# stm32f103.net
KiCad netlist of a schematic drawn in Altium Designer
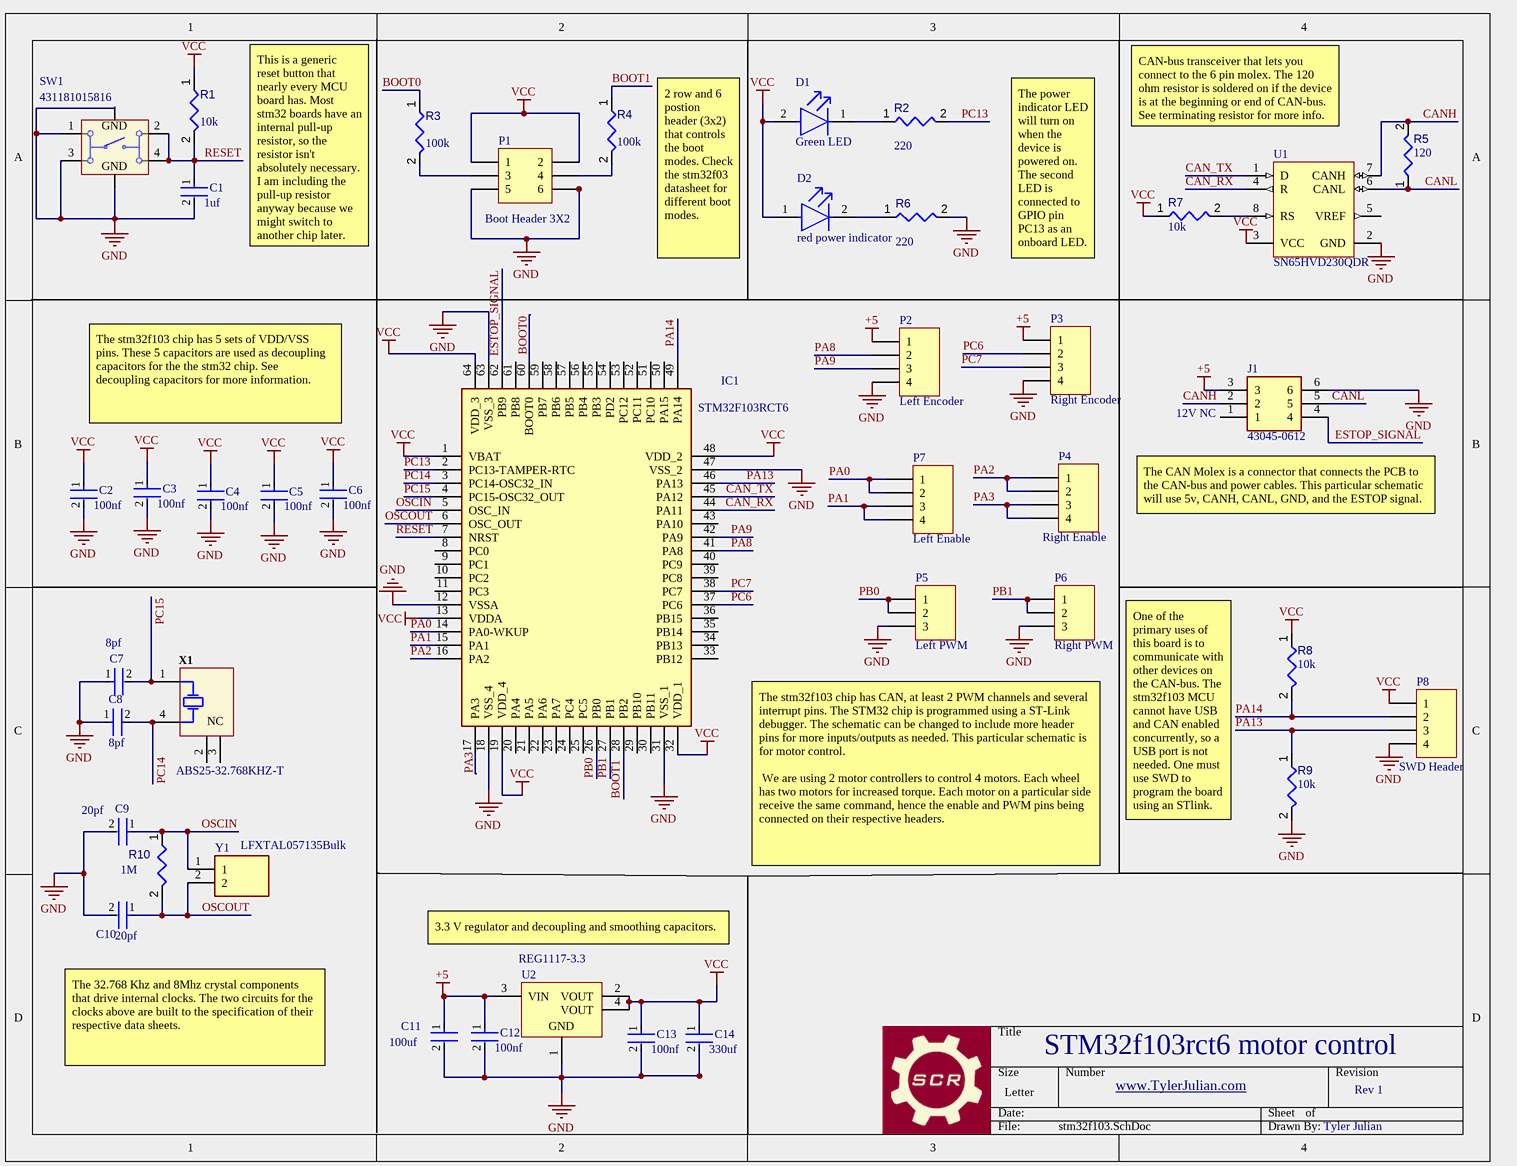
[diagram p0: stm32f103.SchDoc]

(export (version "E")
  (design (tool "Eeschema 10.0.6"))
  (components
    (comp (ref "C1")
      (value "1uf")
      (footprint "FP-GCJ21B-0_3-MFG")
      (description "Multilayer Ceramic Capacitors MLCC - SMD/SMT 0805 1uF 10%, 25VDC,  X7R 15%")
      (fields (field (name "TOLERANCE") "10%"))
      (libsource (lib "Altium Content Vault") (part "02cd4be3c70576c341d710602a673aa"))
    )
    (comp (ref "C2")
      (value "100nf")
      (footprint "FP-GCJ21B-0_3-MFG")
      (description "Multilayer Ceramic Capacitors MLCC - SMD/SMT 0805 1uF 10%, 25VDC,  X7R 15%")
      (fields (field (name "TOLERANCE") "10%"))
      (libsource (lib "Altium Content Vault") (part "02cd4be3c70576c341d710602a673aa"))
    )
    (comp (ref "C3")
      (value "100nf")
      (footprint "FP-GCJ21B-0_3-MFG")
      (description "Multilayer Ceramic Capacitors MLCC - SMD/SMT 0805 1uF 10%, 25VDC,  X7R 15%")
      (fields (field (name "TOLERANCE") "10%"))
      (libsource (lib "Altium Content Vault") (part "02cd4be3c70576c341d710602a673aa"))
    )
    (comp (ref "C4")
      (value "100nf")
      (footprint "FP-GCJ21B-0_3-MFG")
      (description "Multilayer Ceramic Capacitors MLCC - SMD/SMT 0805 1uF 10%, 25VDC,  X7R 15%")
      (fields (field (name "TOLERANCE") "10%"))
      (libsource (lib "Altium Content Vault") (part "02cd4be3c70576c341d710602a673aa"))
    )
    (comp (ref "C5")
      (value "100nf")
      (footprint "FP-GCJ21B-0_3-MFG")
      (description "Multilayer Ceramic Capacitors MLCC - SMD/SMT 0805 1uF 10%, 25VDC,  X7R 15%")
      (fields (field (name "TOLERANCE") "10%"))
      (libsource (lib "Altium Content Vault") (part "02cd4be3c70576c341d710602a673aa"))
    )
    (comp (ref "C6")
      (value "100nf")
      (footprint "FP-GCJ21B-0_3-MFG")
      (description "Multilayer Ceramic Capacitors MLCC - SMD/SMT 0805 1uF 10%, 25VDC,  X7R 15%")
      (fields (field (name "TOLERANCE") "10%"))
      (libsource (lib "Altium Content Vault") (part "02cd4be3c70576c341d710602a673aa"))
    )
    (comp (ref "C7")
      (value "8pf")
      (footprint "FP-GCJ21B-0_3-MFG")
      (description "Multilayer Ceramic Capacitors MLCC - SMD/SMT 0805 1uF 10%, 25VDC,  X7R 15%")
      (fields (field (name "TOLERANCE") "10%"))
      (libsource (lib "Altium Content Vault") (part "02cd4be3c70576c341d710602a673aa"))
    )
    (comp (ref "C8")
      (value "8pf")
      (footprint "FP-GCJ21B-0_3-MFG")
      (description "Multilayer Ceramic Capacitors MLCC - SMD/SMT 0805 1uF 10%, 25VDC,  X7R 15%")
      (fields (field (name "TOLERANCE") "10%"))
      (libsource (lib "Altium Content Vault") (part "02cd4be3c70576c341d710602a673aa"))
    )
    (comp (ref "C9")
      (value "20pf")
      (footprint "FP-GCJ21B-0_3-MFG")
      (description "Multilayer Ceramic Capacitors MLCC - SMD/SMT 0805 1uF 10%, 25VDC,  X7R 15%")
      (fields (field (name "TOLERANCE") "10%"))
      (libsource (lib "Altium Content Vault") (part "02cd4be3c70576c341d710602a673aa"))
    )
    (comp (ref "C10")
      (value "20pf")
      (footprint "FP-GCJ21B-0_3-MFG")
      (description "Multilayer Ceramic Capacitors MLCC - SMD/SMT 0805 1uF 10%, 25VDC,  X7R 15%")
      (fields (field (name "TOLERANCE") "10%"))
      (libsource (lib "Altium Content Vault") (part "02cd4be3c70576c341d710602a673aa"))
    )
    (comp (ref "C11")
      (value "100uf")
      (footprint "FP-GCJ21B-0_3-MFG")
      (description "Multilayer Ceramic Capacitors MLCC - SMD/SMT 0805 1uF 10%, 25VDC,  X7R 15%")
      (fields (field (name "TOLERANCE") "10%"))
      (libsource (lib "Altium Content Vault") (part "02cd4be3c70576c341d710602a673aa"))
    )
    (comp (ref "C12")
      (value "100nf")
      (footprint "FP-GCJ21B-0_3-MFG")
      (description "Multilayer Ceramic Capacitors MLCC - SMD/SMT 0805 1uF 10%, 25VDC,  X7R 15%")
      (fields (field (name "TOLERANCE") "10%"))
      (libsource (lib "Altium Content Vault") (part "02cd4be3c70576c341d710602a673aa"))
    )
    (comp (ref "C13")
      (value "100nf")
      (footprint "FP-GCJ21B-0_3-MFG")
      (description "Multilayer Ceramic Capacitors MLCC - SMD/SMT 0805 1uF 10%, 25VDC,  X7R 15%")
      (fields (field (name "TOLERANCE") "10%"))
      (libsource (lib "Altium Content Vault") (part "02cd4be3c70576c341d710602a673aa"))
    )
    (comp (ref "C14")
      (value "330uf")
      (footprint "FP-GCJ21B-0_3-MFG")
      (description "Multilayer Ceramic Capacitors MLCC - SMD/SMT 0805 1uF 10%, 25VDC,  X7R 15%")
      (fields (field (name "TOLERANCE") "10%"))
      (libsource (lib "Altium Content Vault") (part "02cd4be3c70576c341d710602a673aa"))
    )
    (comp (ref "D1")
      (value "Green LED")
      (footprint "FP-LG_R971-MFG")
      (description "LED GREEN DIFFUSED 0805 SMD\r\nQ62702P5179")
      (libsource (lib "Altium Content Vault") (part "8706943c75ba83719d021d2fdc84c58"))
    )
    (comp (ref "D2")
      (value "red power indicator")
      (footprint "FP-LH_R974-MFG")
      (description "LED RED DIFFUSED 0805 SMD\r\nLH R974-LP-1")
      (libsource (lib "Altium Content Vault") (part "ab1c01a81903e929fc6c44469aada92"))
    )
    (comp (ref "IC1")
      (value "STM32F103RCT6")
      (footprint "SamacSys:QFP50P1200X1200X160-64N")
      (description "Integrated Circuit")
      (fields (field (name "MOUSER2 PART NUMBER") "511-STM32F103RCT6"))
      (libsource (lib "*") (part "STM32F103RCT6"))
    )
    (comp (ref "J1")
      (value "43045-0612")
      (footprint "SamacSys:430450612")
      (description "Connector")
      (libsource (lib "*") (part "43045-0612"))
    )
    (comp (ref "P1")
      (value "Boot Header 3X2")
      (footprint "HDR2X3")
      (description "Header, 3-Pin, Dual row")
      (fields (field (name "PUBLISHER") "Altium Limited"))
      (libsource (lib "Miscellaneous Connectors") (part "Header 3X2"))
    )
    (comp (ref "P2")
      (value "Left Encoder")
      (footprint "HDR1X4")
      (description "Header, 4-Pin")
      (fields (field (name "PUBLISHER") "Altium Limited"))
      (libsource (lib "Miscellaneous Connectors") (part "Header 4"))
    )
    (comp (ref "P3")
      (value "Right Encoder")
      (footprint "HDR1X4")
      (description "Header, 4-Pin")
      (fields (field (name "PUBLISHER") "Altium Limited"))
      (libsource (lib "Miscellaneous Connectors") (part "Header 4"))
    )
    (comp (ref "P4")
      (value "Right Enable")
      (footprint "HDR1X4")
      (description "Header, 4-Pin")
      (fields (field (name "PUBLISHER") "Altium Limited"))
      (libsource (lib "Miscellaneous Connectors") (part "Header 4"))
    )
    (comp (ref "P5")
      (value "Left PWM")
      (footprint "HDR1X3")
      (description "Header, 3-Pin")
      (fields (field (name "PUBLISHER") "Altium Limited"))
      (libsource (lib "Miscellaneous Connectors") (part "Header 3"))
    )
    (comp (ref "P6")
      (value "Right PWM")
      (footprint "HDR1X3")
      (description "Header, 3-Pin")
      (fields (field (name "PUBLISHER") "Altium Limited"))
      (libsource (lib "Miscellaneous Connectors") (part "Header 3"))
    )
    (comp (ref "P7")
      (value "Left Enable")
      (footprint "HDR1X4")
      (description "Header, 4-Pin")
      (fields (field (name "PUBLISHER") "Altium Limited"))
      (libsource (lib "Miscellaneous Connectors") (part "Header 4"))
    )
    (comp (ref "P8")
      (value "SWD Header")
      (footprint "HDR1X4")
      (description "Header, 4-Pin")
      (fields (field (name "PUBLISHER") "Altium Limited"))
      (libsource (lib "Miscellaneous Connectors") (part "Header 4"))
    )
    (comp (ref "R1")
      (value "10k")
      (footprint "RESC2013X50X35ML15T15")
      (description "Chip Resistor, 10 KOhm, +/- 1%, 125 mW, -55 to 155 degC, 0805 (2012 Metric)")
      (fields (field (name "POWER") "125mW") (field (name "TOLERANCE") "1%"))
      (libsource (lib "OU Competitive Robotics Club") (part "RES-2"))
    )
    (comp (ref "R2")
      (value "220")
      (footprint "RESC2013X50X35ML15T15")
      (description "Chip Resistor, 10 KOhm, +/- 1%, 125 mW, -55 to 155 degC, 0805 (2012 Metric)")
      (fields (field (name "POWER") "125mW") (field (name "TOLERANCE") "1%"))
      (libsource (lib "OU Competitive Robotics Club") (part "RES-2"))
    )
    (comp (ref "R3")
      (value "100k")
      (footprint "RESC2013X50X35ML15T15")
      (description "Chip Resistor, 10 KOhm, +/- 1%, 125 mW, -55 to 155 degC, 0805 (2012 Metric)")
      (fields (field (name "POWER") "125mW") (field (name "TOLERANCE") "1%"))
      (libsource (lib "OU Competitive Robotics Club") (part "RES-2"))
    )
    (comp (ref "R4")
      (value "100k")
      (footprint "RESC2013X50X35ML15T15")
      (description "Chip Resistor, 10 KOhm, +/- 1%, 125 mW, -55 to 155 degC, 0805 (2012 Metric)")
      (fields (field (name "POWER") "125mW") (field (name "TOLERANCE") "1%"))
      (libsource (lib "OU Competitive Robotics Club") (part "RES-2"))
    )
    (comp (ref "R5")
      (value "120")
      (footprint "RESC2013X50X35ML15T15")
      (description "Chip Resistor, 10 KOhm, +/- 1%, 125 mW, -55 to 155 degC, 0805 (2012 Metric)")
      (fields (field (name "POWER") "125mW") (field (name "TOLERANCE") "1%"))
      (libsource (lib "OU Competitive Robotics Club") (part "RES-2"))
    )
    (comp (ref "R6")
      (value "220")
      (footprint "RESC2013X50X35ML15T15")
      (description "Chip Resistor, 10 KOhm, +/- 1%, 125 mW, -55 to 155 degC, 0805 (2012 Metric)")
      (fields (field (name "POWER") "125mW") (field (name "TOLERANCE") "1%"))
      (libsource (lib "OU Competitive Robotics Club") (part "RES-2"))
    )
    (comp (ref "R7")
      (value "10k")
      (footprint "RESC2013X50X35ML15T15")
      (description "Chip Resistor, 10 KOhm, +/- 1%, 125 mW, -55 to 155 degC, 0805 (2012 Metric)")
      (fields (field (name "POWER") "125mW") (field (name "TOLERANCE") "1%"))
      (libsource (lib "OU Competitive Robotics Club") (part "RES-2"))
    )
    (comp (ref "R8")
      (value "10k")
      (footprint "RESC2013X50X35ML15T15")
      (description "Chip Resistor, 10 KOhm, +/- 1%, 125 mW, -55 to 155 degC, 0805 (2012 Metric)")
      (fields (field (name "POWER") "125mW") (field (name "TOLERANCE") "1%"))
      (libsource (lib "OU Competitive Robotics Club") (part "RES-2"))
    )
    (comp (ref "R9")
      (value "10k")
      (footprint "RESC2013X50X35ML15T15")
      (description "Chip Resistor, 10 KOhm, +/- 1%, 125 mW, -55 to 155 degC, 0805 (2012 Metric)")
      (fields (field (name "POWER") "125mW") (field (name "TOLERANCE") "1%"))
      (libsource (lib "OU Competitive Robotics Club") (part "RES-2"))
    )
    (comp (ref "R10")
      (value "1M")
      (footprint "RESC2013X50X35ML15T15")
      (description "Chip Resistor, 10 KOhm, +/- 1%, 125 mW, -55 to 155 degC, 0805 (2012 Metric)")
      (fields (field (name "POWER") "125mW") (field (name "TOLERANCE") "1%"))
      (libsource (lib "OU Competitive Robotics Club") (part "RES-2"))
    )
    (comp (ref "SW1")
      (value "431181015816")
      (footprint "431181015816")
      (description "WS-TASV SMD Tact Switch 5X5 mm with ground terminal")
      (fields (field (name "MANUFACTURER") "Wuerth Elektronik"))
      (libsource (lib "Altium Content Vault") (part "WE-TACT-SW-6"))
    )
    (comp (ref "U1")
      (value "SN65HVD230QDR")
      (footprint "D0008A_L")
      (fields (field (name "MANUFACTURER") "Texas Instruments"))
      (libsource (lib "Altium Content Vault") (part "TI-SN65HVD230Q-SOIC_D-8"))
    )
    (comp (ref "U2")
      (value "REG1117-3.3")
      (footprint "DCY0004A_M")
      (fields (field (name "MANUFACTURER") "Texas Instruments"))
      (libsource (lib "Altium Content Vault") (part "TI-REG1117-XXXX"))
    )
    (comp (ref "X1")
      (value "ABS25-32.768KHZ-T")
      (footprint "ABRA-ABS25-4_V")
      (description "Low Frequency Crystal, 32.768 KHz, -40 to 85 degC, 4-Pin SMD, RoHS, Tape and Reel")
      (fields (field (name "TOLERANCE") "20PPM") (field (name "MANUFACTURER") "Abracon"))
      (libsource (lib "Altium Content Vault") (part "ABRA-XTAL_1-4-4"))
    )
    (comp (ref "Y1")
      (value "LFXTAL057135Bulk")
      (footprint "SamacSys:LFXTAL057135Bulk")
      (description "Crystal or Oscillator")
      (libsource (lib "*") (part "LFXTAL057135Bulk"))
    )
  )
  (nets
    (net (code "1") (name "+5") (class "Default")
      (node (ref "C11") (pin "1") (pinfunction "1_1") (pintype "passive"))
      (node (ref "C12") (pin "1") (pinfunction "1_1") (pintype "passive"))
      (node (ref "J1") (pin "3") (pinfunction "3_3") (pintype "passive"))
      (node (ref "P2") (pin "1") (pinfunction "1_1") (pintype "passive"))
      (node (ref "P3") (pin "1") (pinfunction "1_1") (pintype "passive"))
      (node (ref "U2") (pin "3") (pinfunction "VIN_3") (pintype "power_in"))
    )
    (net (code "2") (name "/BOOT0") (class "Default")
      (node (ref "IC1") (pin "60") (pinfunction "BOOT0_60") (pintype "passive"))
      (node (ref "R3") (pin "1") (pinfunction "1_1") (pintype "passive"))
    )
    (net (code "3") (name "/BOOT1") (class "Default")
      (node (ref "IC1") (pin "28") (pinfunction "PB2_28") (pintype "passive"))
      (node (ref "R4") (pin "1") (pinfunction "1_1") (pintype "passive"))
    )
    (net (code "4") (name "/CANH") (class "Default")
      (node (ref "J1") (pin "2") (pinfunction "2_2") (pintype "passive"))
      (node (ref "R5") (pin "2") (pinfunction "2_2") (pintype "passive"))
      (node (ref "U1") (pin "7") (pinfunction "CANH_7") (pintype "bidirectional"))
    )
    (net (code "5") (name "/CANL") (class "Default")
      (node (ref "J1") (pin "5") (pinfunction "5_5") (pintype "passive"))
      (node (ref "R5") (pin "1") (pinfunction "1_1") (pintype "passive"))
      (node (ref "U1") (pin "6") (pinfunction "CANL_6") (pintype "bidirectional"))
    )
    (net (code "6") (name "/CAN_RX") (class "Default")
      (node (ref "IC1") (pin "44") (pinfunction "PA11_44") (pintype "passive"))
      (node (ref "U1") (pin "4") (pinfunction "R_4") (pintype "output"))
    )
    (net (code "7") (name "/CAN_TX") (class "Default")
      (node (ref "IC1") (pin "45") (pinfunction "PA12_45") (pintype "passive"))
      (node (ref "U1") (pin "1") (pinfunction "D_1") (pintype "input"))
    )
    (net (code "8") (name "/ESTOP_SIGNAL") (class "Default")
      (node (ref "IC1") (pin "62") (pinfunction "PB9_62") (pintype "passive"))
      (node (ref "J1") (pin "4") (pinfunction "4_4") (pintype "passive"))
    )
    (net (code "9") (name "/OSCIN") (class "Default")
      (node (ref "C9") (pin "1") (pinfunction "1_1") (pintype "passive"))
      (node (ref "IC1") (pin "5") (pinfunction "OSC_IN_5") (pintype "passive"))
      (node (ref "R10") (pin "1") (pinfunction "1_1") (pintype "passive"))
      (node (ref "Y1") (pin "1") (pinfunction "1_1") (pintype "passive"))
    )
    (net (code "10") (name "/OSCOUT") (class "Default")
      (node (ref "C10") (pin "1") (pinfunction "1_1") (pintype "passive"))
      (node (ref "IC1") (pin "6") (pinfunction "OSC_OUT_6") (pintype "passive"))
      (node (ref "R10") (pin "2") (pinfunction "2_2") (pintype "passive"))
      (node (ref "Y1") (pin "2") (pinfunction "2_2") (pintype "passive"))
    )
    (net (code "11") (name "/PA0") (class "Default")
      (node (ref "IC1") (pin "14") (pinfunction "PA0-WKUP_14") (pintype "passive"))
      (node (ref "P7") (pin "1") (pinfunction "1_1") (pintype "passive"))
      (node (ref "P7") (pin "2") (pinfunction "2_2") (pintype "passive"))
    )
    (net (code "12") (name "/PA1") (class "Default")
      (node (ref "IC1") (pin "15") (pinfunction "PA1_15") (pintype "passive"))
      (node (ref "P7") (pin "3") (pinfunction "3_3") (pintype "passive"))
      (node (ref "P7") (pin "4") (pinfunction "4_4") (pintype "passive"))
    )
    (net (code "13") (name "/PA2") (class "Default")
      (node (ref "IC1") (pin "16") (pinfunction "PA2_16") (pintype "passive"))
      (node (ref "P4") (pin "1") (pinfunction "1_1") (pintype "passive"))
      (node (ref "P4") (pin "2") (pinfunction "2_2") (pintype "passive"))
    )
    (net (code "14") (name "/PA3") (class "Default")
      (node (ref "IC1") (pin "17") (pinfunction "PA3_17") (pintype "passive"))
      (node (ref "P4") (pin "3") (pinfunction "3_3") (pintype "passive"))
      (node (ref "P4") (pin "4") (pinfunction "4_4") (pintype "passive"))
    )
    (net (code "15") (name "/PA8") (class "Default")
      (node (ref "IC1") (pin "41") (pinfunction "PA8_41") (pintype "passive"))
      (node (ref "P2") (pin "2") (pinfunction "2_2") (pintype "passive"))
    )
    (net (code "16") (name "/PA9") (class "Default")
      (node (ref "IC1") (pin "42") (pinfunction "PA9_42") (pintype "passive"))
      (node (ref "P2") (pin "3") (pinfunction "3_3") (pintype "passive"))
    )
    (net (code "17") (name "/PA13") (class "Default")
      (node (ref "IC1") (pin "46") (pinfunction "PA13_46") (pintype "passive"))
      (node (ref "P8") (pin "3") (pinfunction "3_3") (pintype "passive"))
      (node (ref "R9") (pin "1") (pinfunction "1_1") (pintype "passive"))
    )
    (net (code "18") (name "/PA14") (class "Default")
      (node (ref "IC1") (pin "49") (pinfunction "PA14_49") (pintype "passive"))
      (node (ref "P8") (pin "2") (pinfunction "2_2") (pintype "passive"))
      (node (ref "R8") (pin "2") (pinfunction "2_2") (pintype "passive"))
    )
    (net (code "19") (name "/PB0") (class "Default")
      (node (ref "IC1") (pin "26") (pinfunction "PB0_26") (pintype "passive"))
      (node (ref "P5") (pin "1") (pinfunction "1_1") (pintype "passive"))
      (node (ref "P5") (pin "2") (pinfunction "2_2") (pintype "passive"))
    )
    (net (code "20") (name "/PB1") (class "Default")
      (node (ref "IC1") (pin "27") (pinfunction "PB1_27") (pintype "passive"))
      (node (ref "P6") (pin "1") (pinfunction "1_1") (pintype "passive"))
      (node (ref "P6") (pin "2") (pinfunction "2_2") (pintype "passive"))
    )
    (net (code "21") (name "/PC6") (class "Default")
      (node (ref "IC1") (pin "37") (pinfunction "PC6_37") (pintype "passive"))
      (node (ref "P3") (pin "2") (pinfunction "2_2") (pintype "passive"))
    )
    (net (code "22") (name "/PC7") (class "Default")
      (node (ref "IC1") (pin "38") (pinfunction "PC7_38") (pintype "passive"))
      (node (ref "P3") (pin "3") (pinfunction "3_3") (pintype "passive"))
    )
    (net (code "23") (name "/PC13") (class "Default")
      (node (ref "IC1") (pin "2") (pinfunction "PC13-TAMPER-RTC_2") (pintype "passive"))
      (node (ref "R2") (pin "2") (pinfunction "2_2") (pintype "passive"))
    )
    (net (code "24") (name "/PC14") (class "Default")
      (node (ref "C8") (pin "2") (pinfunction "2_2") (pintype "passive"))
      (node (ref "IC1") (pin "3") (pinfunction "PC14-OSC32_IN_3") (pintype "passive"))
      (node (ref "X1") (pin "4") (pinfunction "X2_4") (pintype "passive"))
    )
    (net (code "25") (name "/PC15") (class "Default")
      (node (ref "C7") (pin "2") (pinfunction "2_2") (pintype "passive"))
      (node (ref "IC1") (pin "4") (pinfunction "PC15-OSC32_OUT_4") (pintype "passive"))
      (node (ref "X1") (pin "1") (pinfunction "X1_1") (pintype "passive"))
    )
    (net (code "26") (name "/RESET") (class "Default")
      (node (ref "C1") (pin "1") (pinfunction "1_1") (pintype "passive"))
      (node (ref "IC1") (pin "7") (pinfunction "NRST_7") (pintype "passive"))
      (node (ref "R1") (pin "2") (pinfunction "2_2") (pintype "passive"))
      (node (ref "SW1") (pin "2") (pinfunction "2_2") (pintype "passive"))
      (node (ref "SW1") (pin "4") (pinfunction "4_4") (pintype "passive"))
    )
    (net (code "27") (name "GND") (class "Default")
      (node (ref "C1") (pin "2") (pinfunction "2_2") (pintype "passive"))
      (node (ref "C10") (pin "2") (pinfunction "2_2") (pintype "passive"))
      (node (ref "C11") (pin "2") (pinfunction "2_2") (pintype "passive"))
      (node (ref "C12") (pin "2") (pinfunction "2_2") (pintype "passive"))
      (node (ref "C13") (pin "2") (pinfunction "2_2") (pintype "passive"))
      (node (ref "C14") (pin "2") (pinfunction "2_2") (pintype "passive"))
      (node (ref "C2") (pin "2") (pinfunction "2_2") (pintype "passive"))
      (node (ref "C3") (pin "2") (pinfunction "2_2") (pintype "passive"))
      (node (ref "C4") (pin "2") (pinfunction "2_2") (pintype "passive"))
      (node (ref "C5") (pin "2") (pinfunction "2_2") (pintype "passive"))
      (node (ref "C6") (pin "2") (pinfunction "2_2") (pintype "passive"))
      (node (ref "C7") (pin "1") (pinfunction "1_1") (pintype "passive"))
      (node (ref "C8") (pin "1") (pinfunction "1_1") (pintype "passive"))
      (node (ref "C9") (pin "2") (pinfunction "2_2") (pintype "passive"))
      (node (ref "IC1") (pin "12") (pinfunction "VSSA_12") (pintype "passive"))
      (node (ref "IC1") (pin "18") (pinfunction "VSS_4_18") (pintype "passive"))
      (node (ref "IC1") (pin "31") (pinfunction "VSS_1_31") (pintype "passive"))
      (node (ref "IC1") (pin "47") (pinfunction "VSS_2_47") (pintype "passive"))
      (node (ref "IC1") (pin "63") (pinfunction "VSS_3_63") (pintype "passive"))
      (node (ref "J1") (pin "6") (pinfunction "6_6") (pintype "passive"))
      (node (ref "P1") (pin "5") (pinfunction "5_5") (pintype "passive"))
      (node (ref "P1") (pin "6") (pinfunction "6_6") (pintype "passive"))
      (node (ref "P2") (pin "4") (pinfunction "4_4") (pintype "passive"))
      (node (ref "P3") (pin "4") (pinfunction "4_4") (pintype "passive"))
      (node (ref "P5") (pin "3") (pinfunction "3_3") (pintype "passive"))
      (node (ref "P6") (pin "3") (pinfunction "3_3") (pintype "passive"))
      (node (ref "P8") (pin "4") (pinfunction "4_4") (pintype "passive"))
      (node (ref "R6") (pin "2") (pinfunction "2_2") (pintype "passive"))
      (node (ref "R9") (pin "2") (pinfunction "2_2") (pintype "passive"))
      (node (ref "SW1") (pin "1") (pinfunction "1_1") (pintype "passive"))
      (node (ref "SW1") (pin "3") (pinfunction "3_3") (pintype "passive"))
      (node (ref "SW1") (pin "5") (pinfunction "5_5") (pintype "passive"))
      (node (ref "SW1") (pin "6") (pinfunction "6_6") (pintype "passive"))
      (node (ref "U1") (pin "2") (pinfunction "GND_2") (pintype "power_in"))
      (node (ref "U2") (pin "1") (pinfunction "GND_1") (pintype "power_in"))
    )
    (net (code "28") (name "Net-(D1-C)") (class "Default")
      (node (ref "D1") (pin "1") (pinfunction "C_1") (pintype "passive"))
      (node (ref "R2") (pin "1") (pinfunction "1_1") (pintype "passive"))
    )
    (net (code "29") (name "Net-(D2-C)") (class "Default")
      (node (ref "D2") (pin "2") (pinfunction "C_2") (pintype "passive"))
      (node (ref "R6") (pin "1") (pinfunction "1_1") (pintype "passive"))
    )
    (net (code "30") (name "Net-(P1-Pad3)") (class "Default")
      (node (ref "P1") (pin "3") (pinfunction "3_3") (pintype "passive"))
      (node (ref "R3") (pin "2") (pinfunction "2_2") (pintype "passive"))
    )
    (net (code "31") (name "Net-(P1-Pad4)") (class "Default")
      (node (ref "P1") (pin "4") (pinfunction "4_4") (pintype "passive"))
      (node (ref "R4") (pin "2") (pinfunction "2_2") (pintype "passive"))
    )
    (net (code "32") (name "Net-(U1-RS)") (class "Default")
      (node (ref "R7") (pin "2") (pinfunction "2_2") (pintype "passive"))
      (node (ref "U1") (pin "8") (pinfunction "RS_8") (pintype "input"))
    )
    (net (code "33") (name "VCC") (class "Default")
      (node (ref "C13") (pin "1") (pinfunction "1_1") (pintype "passive"))
      (node (ref "C14") (pin "1") (pinfunction "1_1") (pintype "passive"))
      (node (ref "C2") (pin "1") (pinfunction "1_1") (pintype "passive"))
      (node (ref "C3") (pin "1") (pinfunction "1_1") (pintype "passive"))
      (node (ref "C4") (pin "1") (pinfunction "1_1") (pintype "passive"))
      (node (ref "C5") (pin "1") (pinfunction "1_1") (pintype "passive"))
      (node (ref "C6") (pin "1") (pinfunction "1_1") (pintype "passive"))
      (node (ref "D1") (pin "2") (pinfunction "A_2") (pintype "passive"))
      (node (ref "D2") (pin "1") (pinfunction "A_1") (pintype "passive"))
      (node (ref "IC1") (pin "1") (pinfunction "VBAT_1") (pintype "passive"))
      (node (ref "IC1") (pin "13") (pinfunction "VDDA_13") (pintype "passive"))
      (node (ref "IC1") (pin "19") (pinfunction "VDD_4_19") (pintype "passive"))
      (node (ref "IC1") (pin "32") (pinfunction "VDD_1_32") (pintype "passive"))
      (node (ref "IC1") (pin "48") (pinfunction "VDD_2_48") (pintype "passive"))
      (node (ref "IC1") (pin "64") (pinfunction "VDD_3_64") (pintype "passive"))
      (node (ref "P1") (pin "1") (pinfunction "1_1") (pintype "passive"))
      (node (ref "P1") (pin "2") (pinfunction "2_2") (pintype "passive"))
      (node (ref "P8") (pin "1") (pinfunction "1_1") (pintype "passive"))
      (node (ref "R1") (pin "1") (pinfunction "1_1") (pintype "passive"))
      (node (ref "R7") (pin "1") (pinfunction "1_1") (pintype "passive"))
      (node (ref "R8") (pin "1") (pinfunction "1_1") (pintype "passive"))
      (node (ref "U1") (pin "3") (pinfunction "VCC_3") (pintype "power_in"))
      (node (ref "U2") (pin "2") (pinfunction "VOUT_2") (pintype "power_in"))
      (node (ref "U2") (pin "4") (pinfunction "VOUT_4") (pintype "power_in"))
    )
    (net (code "34") (name "unconnected-(IC1-PA4-Pad20)") (class "Default")
      (node (ref "IC1") (pin "20") (pinfunction "PA4_20") (pintype "passive"))
    )
    (net (code "35") (name "unconnected-(IC1-PA5-Pad21)") (class "Default")
      (node (ref "IC1") (pin "21") (pinfunction "PA5_21") (pintype "passive"))
    )
    (net (code "36") (name "unconnected-(IC1-PA6-Pad22)") (class "Default")
      (node (ref "IC1") (pin "22") (pinfunction "PA6_22") (pintype "passive"))
    )
    (net (code "37") (name "unconnected-(IC1-PA7-Pad23)") (class "Default")
      (node (ref "IC1") (pin "23") (pinfunction "PA7_23") (pintype "passive"))
    )
    (net (code "38") (name "unconnected-(IC1-PA10-Pad43)") (class "Default")
      (node (ref "IC1") (pin "43") (pinfunction "PA10_43") (pintype "passive"))
    )
    (net (code "39") (name "unconnected-(IC1-PA15-Pad50)") (class "Default")
      (node (ref "IC1") (pin "50") (pinfunction "PA15_50") (pintype "passive"))
    )
    (net (code "40") (name "unconnected-(IC1-PB3-Pad55)") (class "Default")
      (node (ref "IC1") (pin "55") (pinfunction "PB3_55") (pintype "passive"))
    )
    (net (code "41") (name "unconnected-(IC1-PB4-Pad56)") (class "Default")
      (node (ref "IC1") (pin "56") (pinfunction "PB4_56") (pintype "passive"))
    )
    (net (code "42") (name "unconnected-(IC1-PB5-Pad57)") (class "Default")
      (node (ref "IC1") (pin "57") (pinfunction "PB5_57") (pintype "passive"))
    )
    (net (code "43") (name "unconnected-(IC1-PB6-Pad58)") (class "Default")
      (node (ref "IC1") (pin "58") (pinfunction "PB6_58") (pintype "passive"))
    )
    (net (code "44") (name "unconnected-(IC1-PB7-Pad59)") (class "Default")
      (node (ref "IC1") (pin "59") (pinfunction "PB7_59") (pintype "passive"))
    )
    (net (code "45") (name "unconnected-(IC1-PB8-Pad61)") (class "Default")
      (node (ref "IC1") (pin "61") (pinfunction "PB8_61") (pintype "passive"))
    )
    (net (code "46") (name "unconnected-(IC1-PB10-Pad29)") (class "Default")
      (node (ref "IC1") (pin "29") (pinfunction "PB10_29") (pintype "passive"))
    )
    (net (code "47") (name "unconnected-(IC1-PB11-Pad30)") (class "Default")
      (node (ref "IC1") (pin "30") (pinfunction "PB11_30") (pintype "passive"))
    )
    (net (code "48") (name "unconnected-(IC1-PB12-Pad33)") (class "Default")
      (node (ref "IC1") (pin "33") (pinfunction "PB12_33") (pintype "passive"))
    )
    (net (code "49") (name "unconnected-(IC1-PB13-Pad34)") (class "Default")
      (node (ref "IC1") (pin "34") (pinfunction "PB13_34") (pintype "passive"))
    )
    (net (code "50") (name "unconnected-(IC1-PB14-Pad35)") (class "Default")
      (node (ref "IC1") (pin "35") (pinfunction "PB14_35") (pintype "passive"))
    )
    (net (code "51") (name "unconnected-(IC1-PB15-Pad36)") (class "Default")
      (node (ref "IC1") (pin "36") (pinfunction "PB15_36") (pintype "passive"))
    )
    (net (code "52") (name "unconnected-(IC1-PC0-Pad8)") (class "Default")
      (node (ref "IC1") (pin "8") (pinfunction "PC0_8") (pintype "passive"))
    )
    (net (code "53") (name "unconnected-(IC1-PC1-Pad9)") (class "Default")
      (node (ref "IC1") (pin "9") (pinfunction "PC1_9") (pintype "passive"))
    )
    (net (code "54") (name "unconnected-(IC1-PC2-Pad10)") (class "Default")
      (node (ref "IC1") (pin "10") (pinfunction "PC2_10") (pintype "passive"))
    )
    (net (code "55") (name "unconnected-(IC1-PC3-Pad11)") (class "Default")
      (node (ref "IC1") (pin "11") (pinfunction "PC3_11") (pintype "passive"))
    )
    (net (code "56") (name "unconnected-(IC1-PC4-Pad24)") (class "Default")
      (node (ref "IC1") (pin "24") (pinfunction "PC4_24") (pintype "passive"))
    )
    (net (code "57") (name "unconnected-(IC1-PC5-Pad25)") (class "Default")
      (node (ref "IC1") (pin "25") (pinfunction "PC5_25") (pintype "passive"))
    )
    (net (code "58") (name "unconnected-(IC1-PC8-Pad39)") (class "Default")
      (node (ref "IC1") (pin "39") (pinfunction "PC8_39") (pintype "passive"))
    )
    (net (code "59") (name "unconnected-(IC1-PC9-Pad40)") (class "Default")
      (node (ref "IC1") (pin "40") (pinfunction "PC9_40") (pintype "passive"))
    )
    (net (code "60") (name "unconnected-(IC1-PC10-Pad51)") (class "Default")
      (node (ref "IC1") (pin "51") (pinfunction "PC10_51") (pintype "passive"))
    )
    (net (code "61") (name "unconnected-(IC1-PC11-Pad52)") (class "Default")
      (node (ref "IC1") (pin "52") (pinfunction "PC11_52") (pintype "passive"))
    )
    (net (code "62") (name "unconnected-(IC1-PC12-Pad53)") (class "Default")
      (node (ref "IC1") (pin "53") (pinfunction "PC12_53") (pintype "passive"))
    )
    (net (code "63") (name "unconnected-(IC1-PD2-Pad54)") (class "Default")
      (node (ref "IC1") (pin "54") (pinfunction "PD2_54") (pintype "passive"))
    )
    (net (code "64") (name "unconnected-(J1-Pad1)") (class "Default")
      (node (ref "J1") (pin "1") (pinfunction "1_1") (pintype "passive"))
    )
    (net (code "65") (name "unconnected-(U1-VREF-Pad5)") (class "Default")
      (node (ref "U1") (pin "5") (pinfunction "VREF_5") (pintype "output"))
    )
    (net (code "66") (name "unconnected-(X1-NC-Pad2)") (class "Default")
      (node (ref "X1") (pin "2") (pinfunction "NC_2") (pintype "passive"))
    )
    (net (code "67") (name "unconnected-(X1-NC-Pad3)") (class "Default")
      (node (ref "X1") (pin "3") (pinfunction "NC_3") (pintype "passive"))
    )
  )
)
